# BottomSide.net
KiCad netlist of a schematic drawn in Altium Designer
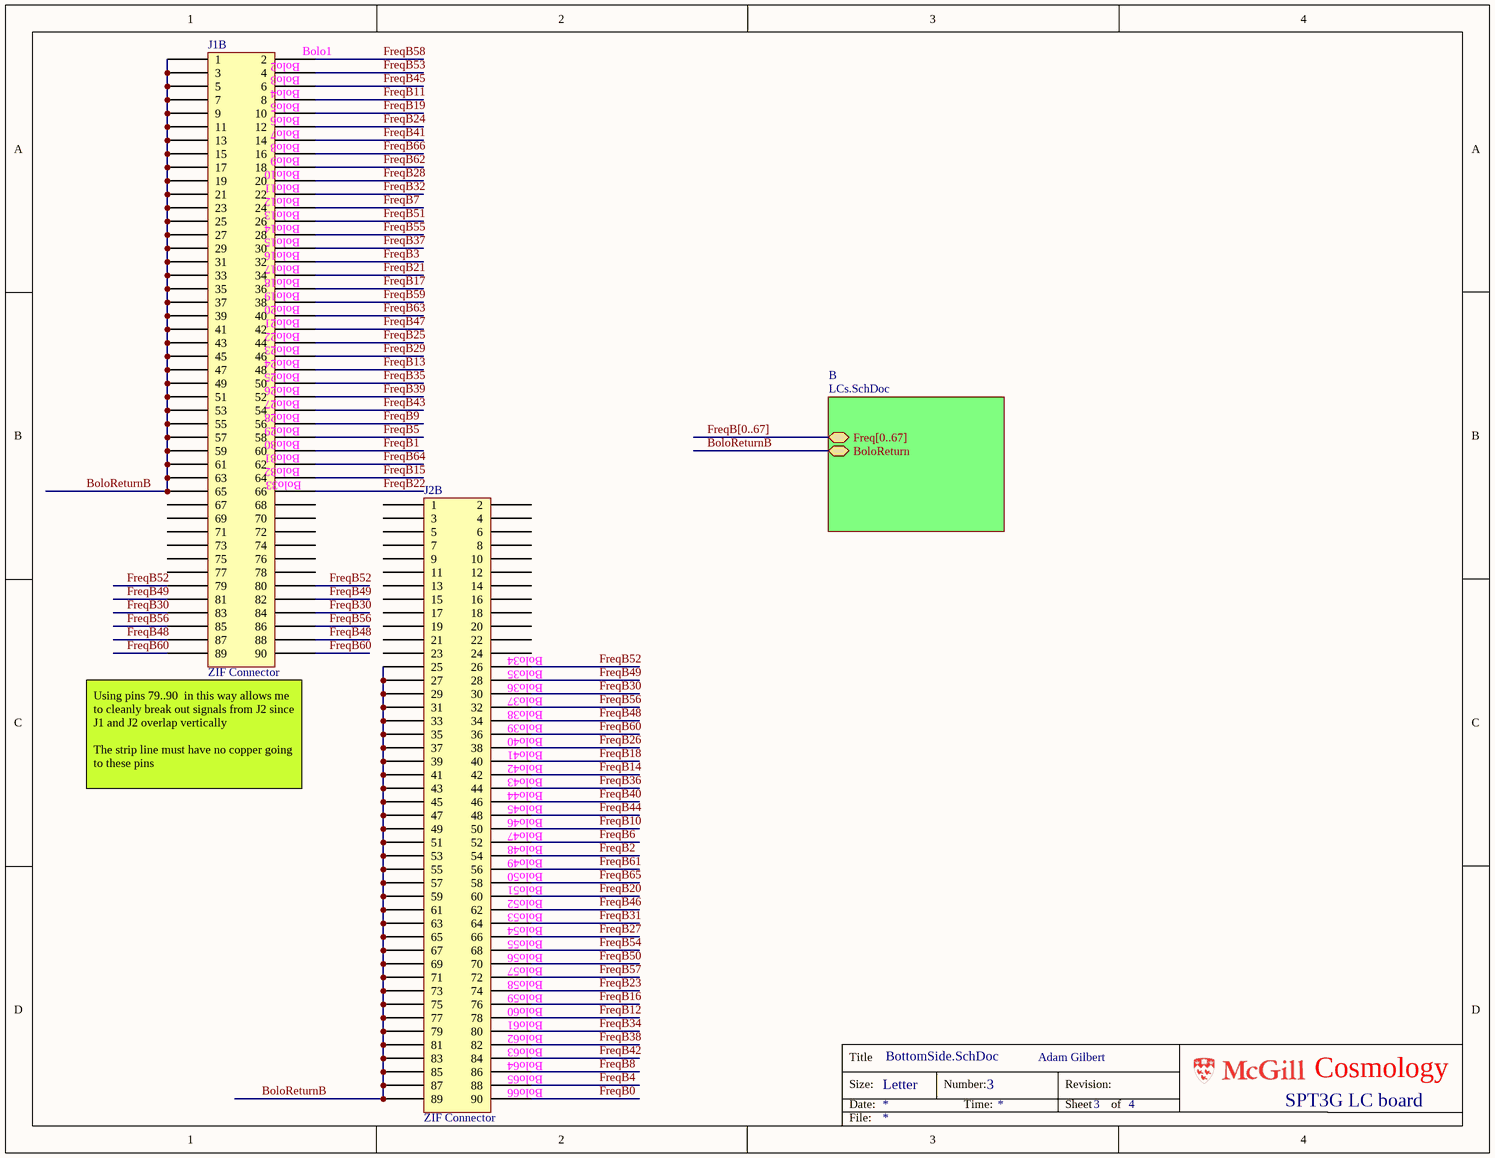
[diagram p0: BottomSide.SchDoc]

(export (version "E")
  (design (tool "Eeschema 10.0.6"))
  (components
    (comp (ref "J1B")
      (value "ZIF Connector")
      (footprint "LCBoard_ZIFCon")
      (libsource (lib "SPT3G_LCBoard") (part "LCboard_FH16-90S-0.3SHW(05)"))
    )
    (comp (ref "J2B")
      (value "ZIF Connector")
      (footprint "LCBoard_ZIFCon")
      (libsource (lib "SPT3G_LCBoard") (part "LCboard_FH16-90S-0.3SHW(05)"))
    )
  )
  (nets
    (net (code "3") (name "/BoloReturnB") (class "Default")
      (node (ref "J1B") (pin "1") (pinfunction "1_1") (pintype "passive"))
      (node (ref "J1B") (pin "11") (pinfunction "11_11") (pintype "passive"))
      (node (ref "J1B") (pin "13") (pinfunction "13_13") (pintype "passive"))
      (node (ref "J1B") (pin "15") (pinfunction "15_15") (pintype "passive"))
      (node (ref "J1B") (pin "17") (pinfunction "17_17") (pintype "passive"))
      (node (ref "J1B") (pin "19") (pinfunction "19_19") (pintype "passive"))
      (node (ref "J1B") (pin "21") (pinfunction "21_21") (pintype "passive"))
      (node (ref "J1B") (pin "23") (pinfunction "23_23") (pintype "passive"))
      (node (ref "J1B") (pin "25") (pinfunction "25_25") (pintype "passive"))
      (node (ref "J1B") (pin "27") (pinfunction "27_27") (pintype "passive"))
      (node (ref "J1B") (pin "29") (pinfunction "29_29") (pintype "passive"))
      (node (ref "J1B") (pin "3") (pinfunction "3_3") (pintype "passive"))
      (node (ref "J1B") (pin "31") (pinfunction "31_31") (pintype "passive"))
      (node (ref "J1B") (pin "33") (pinfunction "33_33") (pintype "passive"))
      (node (ref "J1B") (pin "35") (pinfunction "35_35") (pintype "passive"))
      (node (ref "J1B") (pin "37") (pinfunction "37_37") (pintype "passive"))
      (node (ref "J1B") (pin "39") (pinfunction "39_39") (pintype "passive"))
      (node (ref "J1B") (pin "41") (pinfunction "41_41") (pintype "passive"))
      (node (ref "J1B") (pin "43") (pinfunction "43_43") (pintype "passive"))
      (node (ref "J1B") (pin "45") (pinfunction "45_45") (pintype "passive"))
      (node (ref "J1B") (pin "47") (pinfunction "47_47") (pintype "passive"))
      (node (ref "J1B") (pin "49") (pinfunction "49_49") (pintype "passive"))
      (node (ref "J1B") (pin "5") (pinfunction "5_5") (pintype "passive"))
      (node (ref "J1B") (pin "51") (pinfunction "51_51") (pintype "passive"))
      (node (ref "J1B") (pin "53") (pinfunction "53_53") (pintype "passive"))
      (node (ref "J1B") (pin "55") (pinfunction "55_55") (pintype "passive"))
      (node (ref "J1B") (pin "57") (pinfunction "57_57") (pintype "passive"))
      (node (ref "J1B") (pin "59") (pinfunction "59_59") (pintype "passive"))
      (node (ref "J1B") (pin "61") (pinfunction "61_61") (pintype "passive"))
      (node (ref "J1B") (pin "63") (pinfunction "63_63") (pintype "passive"))
      (node (ref "J1B") (pin "65") (pinfunction "65_65") (pintype "passive"))
      (node (ref "J1B") (pin "7") (pinfunction "7_7") (pintype "passive"))
      (node (ref "J1B") (pin "9") (pinfunction "9_9") (pintype "passive"))
      (node (ref "J2B") (pin "25") (pinfunction "25_25") (pintype "passive"))
      (node (ref "J2B") (pin "27") (pinfunction "27_27") (pintype "passive"))
      (node (ref "J2B") (pin "29") (pinfunction "29_29") (pintype "passive"))
      (node (ref "J2B") (pin "31") (pinfunction "31_31") (pintype "passive"))
      (node (ref "J2B") (pin "33") (pinfunction "33_33") (pintype "passive"))
      (node (ref "J2B") (pin "35") (pinfunction "35_35") (pintype "passive"))
      (node (ref "J2B") (pin "37") (pinfunction "37_37") (pintype "passive"))
      (node (ref "J2B") (pin "39") (pinfunction "39_39") (pintype "passive"))
      (node (ref "J2B") (pin "41") (pinfunction "41_41") (pintype "passive"))
      (node (ref "J2B") (pin "43") (pinfunction "43_43") (pintype "passive"))
      (node (ref "J2B") (pin "45") (pinfunction "45_45") (pintype "passive"))
      (node (ref "J2B") (pin "47") (pinfunction "47_47") (pintype "passive"))
      (node (ref "J2B") (pin "49") (pinfunction "49_49") (pintype "passive"))
      (node (ref "J2B") (pin "51") (pinfunction "51_51") (pintype "passive"))
      (node (ref "J2B") (pin "53") (pinfunction "53_53") (pintype "passive"))
      (node (ref "J2B") (pin "55") (pinfunction "55_55") (pintype "passive"))
      (node (ref "J2B") (pin "57") (pinfunction "57_57") (pintype "passive"))
      (node (ref "J2B") (pin "59") (pinfunction "59_59") (pintype "passive"))
      (node (ref "J2B") (pin "61") (pinfunction "61_61") (pintype "passive"))
      (node (ref "J2B") (pin "63") (pinfunction "63_63") (pintype "passive"))
      (node (ref "J2B") (pin "65") (pinfunction "65_65") (pintype "passive"))
      (node (ref "J2B") (pin "67") (pinfunction "67_67") (pintype "passive"))
      (node (ref "J2B") (pin "69") (pinfunction "69_69") (pintype "passive"))
      (node (ref "J2B") (pin "71") (pinfunction "71_71") (pintype "passive"))
      (node (ref "J2B") (pin "73") (pinfunction "73_73") (pintype "passive"))
      (node (ref "J2B") (pin "75") (pinfunction "75_75") (pintype "passive"))
      (node (ref "J2B") (pin "77") (pinfunction "77_77") (pintype "passive"))
      (node (ref "J2B") (pin "79") (pinfunction "79_79") (pintype "passive"))
      (node (ref "J2B") (pin "81") (pinfunction "81_81") (pintype "passive"))
      (node (ref "J2B") (pin "83") (pinfunction "83_83") (pintype "passive"))
      (node (ref "J2B") (pin "85") (pinfunction "85_85") (pintype "passive"))
      (node (ref "J2B") (pin "87") (pinfunction "87_87") (pintype "passive"))
      (node (ref "J2B") (pin "89") (pinfunction "89_89") (pintype "passive"))
    )
    (net (code "4") (name "/FreqB0") (class "Default")
      (node (ref "J2B") (pin "90") (pinfunction "90_90") (pintype "passive"))
    )
    (net (code "5") (name "/FreqB1") (class "Default")
      (node (ref "J1B") (pin "60") (pinfunction "60_60") (pintype "passive"))
    )
    (net (code "6") (name "/FreqB2") (class "Default")
      (node (ref "J2B") (pin "54") (pinfunction "54_54") (pintype "passive"))
    )
    (net (code "7") (name "/FreqB3") (class "Default")
      (node (ref "J1B") (pin "32") (pinfunction "32_32") (pintype "passive"))
    )
    (net (code "8") (name "/FreqB4") (class "Default")
      (node (ref "J2B") (pin "88") (pinfunction "88_88") (pintype "passive"))
    )
    (net (code "9") (name "/FreqB5") (class "Default")
      (node (ref "J1B") (pin "58") (pinfunction "58_58") (pintype "passive"))
    )
    (net (code "10") (name "/FreqB6") (class "Default")
      (node (ref "J2B") (pin "52") (pinfunction "52_52") (pintype "passive"))
    )
    (net (code "11") (name "/FreqB7") (class "Default")
      (node (ref "J1B") (pin "24") (pinfunction "24_24") (pintype "passive"))
    )
    (net (code "12") (name "/FreqB8") (class "Default")
      (node (ref "J2B") (pin "86") (pinfunction "86_86") (pintype "passive"))
    )
    (net (code "13") (name "/FreqB9") (class "Default")
      (node (ref "J1B") (pin "56") (pinfunction "56_56") (pintype "passive"))
    )
    (net (code "14") (name "/FreqB10") (class "Default")
      (node (ref "J2B") (pin "50") (pinfunction "50_50") (pintype "passive"))
    )
    (net (code "15") (name "/FreqB11") (class "Default")
      (node (ref "J1B") (pin "8") (pinfunction "8_8") (pintype "passive"))
    )
    (net (code "16") (name "/FreqB12") (class "Default")
      (node (ref "J2B") (pin "78") (pinfunction "78_78") (pintype "passive"))
    )
    (net (code "17") (name "/FreqB13") (class "Default")
      (node (ref "J1B") (pin "48") (pinfunction "48_48") (pintype "passive"))
    )
    (net (code "18") (name "/FreqB14") (class "Default")
      (node (ref "J2B") (pin "42") (pinfunction "42_42") (pintype "passive"))
    )
    (net (code "19") (name "/FreqB15") (class "Default")
      (node (ref "J1B") (pin "64") (pinfunction "64_64") (pintype "passive"))
    )
    (net (code "20") (name "/FreqB16") (class "Default")
      (node (ref "J2B") (pin "76") (pinfunction "76_76") (pintype "passive"))
    )
    (net (code "21") (name "/FreqB17") (class "Default")
      (node (ref "J1B") (pin "36") (pinfunction "36_36") (pintype "passive"))
    )
    (net (code "22") (name "/FreqB18") (class "Default")
      (node (ref "J2B") (pin "40") (pinfunction "40_40") (pintype "passive"))
    )
    (net (code "23") (name "/FreqB19") (class "Default")
      (node (ref "J1B") (pin "10") (pinfunction "10_10") (pintype "passive"))
    )
    (net (code "24") (name "/FreqB20") (class "Default")
      (node (ref "J2B") (pin "60") (pinfunction "60_60") (pintype "passive"))
    )
    (net (code "25") (name "/FreqB21") (class "Default")
      (node (ref "J1B") (pin "34") (pinfunction "34_34") (pintype "passive"))
    )
    (net (code "26") (name "/FreqB22") (class "Default")
      (node (ref "J1B") (pin "66") (pinfunction "66_66") (pintype "passive"))
    )
    (net (code "27") (name "/FreqB23") (class "Default")
      (node (ref "J2B") (pin "74") (pinfunction "74_74") (pintype "passive"))
    )
    (net (code "28") (name "/FreqB24") (class "Default")
      (node (ref "J1B") (pin "12") (pinfunction "12_12") (pintype "passive"))
    )
    (net (code "29") (name "/FreqB25") (class "Default")
      (node (ref "J1B") (pin "44") (pinfunction "44_44") (pintype "passive"))
    )
    (net (code "30") (name "/FreqB26") (class "Default")
      (node (ref "J2B") (pin "38") (pinfunction "38_38") (pintype "passive"))
    )
    (net (code "31") (name "/FreqB27") (class "Default")
      (node (ref "J2B") (pin "66") (pinfunction "66_66") (pintype "passive"))
    )
    (net (code "32") (name "/FreqB28") (class "Default")
      (node (ref "J1B") (pin "20") (pinfunction "20_20") (pintype "passive"))
    )
    (net (code "33") (name "/FreqB29") (class "Default")
      (node (ref "J1B") (pin "46") (pinfunction "46_46") (pintype "passive"))
    )
    (net (code "34") (name "/FreqB30") (class "Default")
      (node (ref "J1B") (pin "83") (pinfunction "83_83") (pintype "passive"))
      (node (ref "J1B") (pin "84") (pinfunction "84_84") (pintype "passive"))
      (node (ref "J2B") (pin "30") (pinfunction "30_30") (pintype "passive"))
    )
    (net (code "35") (name "/FreqB31") (class "Default")
      (node (ref "J2B") (pin "64") (pinfunction "64_64") (pintype "passive"))
    )
    (net (code "36") (name "/FreqB32") (class "Default")
      (node (ref "J1B") (pin "22") (pinfunction "22_22") (pintype "passive"))
    )
    (net (code "37") (name "/FreqB34") (class "Default")
      (node (ref "J2B") (pin "80") (pinfunction "80_80") (pintype "passive"))
    )
    (net (code "38") (name "/FreqB35") (class "Default")
      (node (ref "J1B") (pin "50") (pinfunction "50_50") (pintype "passive"))
    )
    (net (code "39") (name "/FreqB36") (class "Default")
      (node (ref "J2B") (pin "44") (pinfunction "44_44") (pintype "passive"))
    )
    (net (code "40") (name "/FreqB37") (class "Default")
      (node (ref "J1B") (pin "30") (pinfunction "30_30") (pintype "passive"))
    )
    (net (code "41") (name "/FreqB38") (class "Default")
      (node (ref "J2B") (pin "82") (pinfunction "82_82") (pintype "passive"))
    )
    (net (code "42") (name "/FreqB39") (class "Default")
      (node (ref "J1B") (pin "52") (pinfunction "52_52") (pintype "passive"))
    )
    (net (code "43") (name "/FreqB40") (class "Default")
      (node (ref "J2B") (pin "46") (pinfunction "46_46") (pintype "passive"))
    )
    (net (code "44") (name "/FreqB41") (class "Default")
      (node (ref "J1B") (pin "14") (pinfunction "14_14") (pintype "passive"))
    )
    (net (code "45") (name "/FreqB42") (class "Default")
      (node (ref "J2B") (pin "84") (pinfunction "84_84") (pintype "passive"))
    )
    (net (code "46") (name "/FreqB43") (class "Default")
      (node (ref "J1B") (pin "54") (pinfunction "54_54") (pintype "passive"))
    )
    (net (code "47") (name "/FreqB44") (class "Default")
      (node (ref "J2B") (pin "48") (pinfunction "48_48") (pintype "passive"))
    )
    (net (code "48") (name "/FreqB45") (class "Default")
      (node (ref "J1B") (pin "6") (pinfunction "6_6") (pintype "passive"))
    )
    (net (code "49") (name "/FreqB46") (class "Default")
      (node (ref "J2B") (pin "62") (pinfunction "62_62") (pintype "passive"))
    )
    (net (code "50") (name "/FreqB47") (class "Default")
      (node (ref "J1B") (pin "42") (pinfunction "42_42") (pintype "passive"))
    )
    (net (code "51") (name "/FreqB48") (class "Default")
      (node (ref "J1B") (pin "87") (pinfunction "87_87") (pintype "passive"))
      (node (ref "J1B") (pin "88") (pinfunction "88_88") (pintype "passive"))
      (node (ref "J2B") (pin "34") (pinfunction "34_34") (pintype "passive"))
    )
    (net (code "52") (name "/FreqB49") (class "Default")
      (node (ref "J1B") (pin "81") (pinfunction "81_81") (pintype "passive"))
      (node (ref "J1B") (pin "82") (pinfunction "82_82") (pintype "passive"))
      (node (ref "J2B") (pin "28") (pinfunction "28_28") (pintype "passive"))
    )
    (net (code "53") (name "/FreqB50") (class "Default")
      (node (ref "J2B") (pin "70") (pinfunction "70_70") (pintype "passive"))
    )
    (net (code "54") (name "/FreqB51") (class "Default")
      (node (ref "J1B") (pin "26") (pinfunction "26_26") (pintype "passive"))
    )
    (net (code "55") (name "/FreqB52") (class "Default")
      (node (ref "J1B") (pin "79") (pinfunction "79_79") (pintype "passive"))
      (node (ref "J1B") (pin "80") (pinfunction "80_80") (pintype "passive"))
      (node (ref "J2B") (pin "26") (pinfunction "26_26") (pintype "passive"))
    )
    (net (code "56") (name "/FreqB53") (class "Default")
      (node (ref "J1B") (pin "4") (pinfunction "4_4") (pintype "passive"))
    )
    (net (code "57") (name "/FreqB54") (class "Default")
      (node (ref "J2B") (pin "68") (pinfunction "68_68") (pintype "passive"))
    )
    (net (code "58") (name "/FreqB55") (class "Default")
      (node (ref "J1B") (pin "28") (pinfunction "28_28") (pintype "passive"))
    )
    (net (code "59") (name "/FreqB56") (class "Default")
      (node (ref "J1B") (pin "85") (pinfunction "85_85") (pintype "passive"))
      (node (ref "J1B") (pin "86") (pinfunction "86_86") (pintype "passive"))
      (node (ref "J2B") (pin "32") (pinfunction "32_32") (pintype "passive"))
    )
    (net (code "60") (name "/FreqB57") (class "Default")
      (node (ref "J2B") (pin "72") (pinfunction "72_72") (pintype "passive"))
    )
    (net (code "61") (name "/FreqB58") (class "Default")
      (node (ref "J1B") (pin "2") (pinfunction "2_2") (pintype "passive"))
    )
    (net (code "62") (name "/FreqB59") (class "Default")
      (node (ref "J1B") (pin "38") (pinfunction "38_38") (pintype "passive"))
    )
    (net (code "63") (name "/FreqB60") (class "Default")
      (node (ref "J1B") (pin "89") (pinfunction "89_89") (pintype "passive"))
      (node (ref "J1B") (pin "90") (pinfunction "90_90") (pintype "passive"))
      (node (ref "J2B") (pin "36") (pinfunction "36_36") (pintype "passive"))
    )
    (net (code "64") (name "/FreqB61") (class "Default")
      (node (ref "J2B") (pin "56") (pinfunction "56_56") (pintype "passive"))
    )
    (net (code "65") (name "/FreqB62") (class "Default")
      (node (ref "J1B") (pin "18") (pinfunction "18_18") (pintype "passive"))
    )
    (net (code "66") (name "/FreqB63") (class "Default")
      (node (ref "J1B") (pin "40") (pinfunction "40_40") (pintype "passive"))
    )
    (net (code "67") (name "/FreqB64") (class "Default")
      (node (ref "J1B") (pin "62") (pinfunction "62_62") (pintype "passive"))
    )
    (net (code "68") (name "/FreqB65") (class "Default")
      (node (ref "J2B") (pin "58") (pinfunction "58_58") (pintype "passive"))
    )
    (net (code "69") (name "/FreqB66") (class "Default")
      (node (ref "J1B") (pin "16") (pinfunction "16_16") (pintype "passive"))
    )
    (net (code "71") (name "unconnected-(J1B-Pad67)") (class "Default")
      (node (ref "J1B") (pin "67") (pinfunction "67_67") (pintype "passive"))
    )
    (net (code "72") (name "unconnected-(J1B-Pad68)") (class "Default")
      (node (ref "J1B") (pin "68") (pinfunction "68_68") (pintype "passive"))
    )
    (net (code "73") (name "unconnected-(J1B-Pad69)") (class "Default")
      (node (ref "J1B") (pin "69") (pinfunction "69_69") (pintype "passive"))
    )
    (net (code "74") (name "unconnected-(J1B-Pad70)") (class "Default")
      (node (ref "J1B") (pin "70") (pinfunction "70_70") (pintype "passive"))
    )
    (net (code "75") (name "unconnected-(J1B-Pad71)") (class "Default")
      (node (ref "J1B") (pin "71") (pinfunction "71_71") (pintype "passive"))
    )
    (net (code "76") (name "unconnected-(J1B-Pad72)") (class "Default")
      (node (ref "J1B") (pin "72") (pinfunction "72_72") (pintype "passive"))
    )
    (net (code "77") (name "unconnected-(J1B-Pad73)") (class "Default")
      (node (ref "J1B") (pin "73") (pinfunction "73_73") (pintype "passive"))
    )
    (net (code "78") (name "unconnected-(J1B-Pad74)") (class "Default")
      (node (ref "J1B") (pin "74") (pinfunction "74_74") (pintype "passive"))
    )
    (net (code "79") (name "unconnected-(J1B-Pad75)") (class "Default")
      (node (ref "J1B") (pin "75") (pinfunction "75_75") (pintype "passive"))
    )
    (net (code "80") (name "unconnected-(J1B-Pad76)") (class "Default")
      (node (ref "J1B") (pin "76") (pinfunction "76_76") (pintype "passive"))
    )
    (net (code "81") (name "unconnected-(J1B-Pad77)") (class "Default")
      (node (ref "J1B") (pin "77") (pinfunction "77_77") (pintype "passive"))
    )
    (net (code "82") (name "unconnected-(J1B-Pad78)") (class "Default")
      (node (ref "J1B") (pin "78") (pinfunction "78_78") (pintype "passive"))
    )
    (net (code "83") (name "unconnected-(J2B-Pad1)") (class "Default")
      (node (ref "J2B") (pin "1") (pinfunction "1_1") (pintype "passive"))
    )
    (net (code "84") (name "unconnected-(J2B-Pad2)") (class "Default")
      (node (ref "J2B") (pin "2") (pinfunction "2_2") (pintype "passive"))
    )
    (net (code "85") (name "unconnected-(J2B-Pad3)") (class "Default")
      (node (ref "J2B") (pin "3") (pinfunction "3_3") (pintype "passive"))
    )
    (net (code "86") (name "unconnected-(J2B-Pad4)") (class "Default")
      (node (ref "J2B") (pin "4") (pinfunction "4_4") (pintype "passive"))
    )
    (net (code "87") (name "unconnected-(J2B-Pad5)") (class "Default")
      (node (ref "J2B") (pin "5") (pinfunction "5_5") (pintype "passive"))
    )
    (net (code "88") (name "unconnected-(J2B-Pad6)") (class "Default")
      (node (ref "J2B") (pin "6") (pinfunction "6_6") (pintype "passive"))
    )
    (net (code "89") (name "unconnected-(J2B-Pad7)") (class "Default")
      (node (ref "J2B") (pin "7") (pinfunction "7_7") (pintype "passive"))
    )
    (net (code "90") (name "unconnected-(J2B-Pad8)") (class "Default")
      (node (ref "J2B") (pin "8") (pinfunction "8_8") (pintype "passive"))
    )
    (net (code "91") (name "unconnected-(J2B-Pad9)") (class "Default")
      (node (ref "J2B") (pin "9") (pinfunction "9_9") (pintype "passive"))
    )
    (net (code "92") (name "unconnected-(J2B-Pad10)") (class "Default")
      (node (ref "J2B") (pin "10") (pinfunction "10_10") (pintype "passive"))
    )
    (net (code "93") (name "unconnected-(J2B-Pad11)") (class "Default")
      (node (ref "J2B") (pin "11") (pinfunction "11_11") (pintype "passive"))
    )
    (net (code "94") (name "unconnected-(J2B-Pad12)") (class "Default")
      (node (ref "J2B") (pin "12") (pinfunction "12_12") (pintype "passive"))
    )
    (net (code "95") (name "unconnected-(J2B-Pad13)") (class "Default")
      (node (ref "J2B") (pin "13") (pinfunction "13_13") (pintype "passive"))
    )
    (net (code "96") (name "unconnected-(J2B-Pad14)") (class "Default")
      (node (ref "J2B") (pin "14") (pinfunction "14_14") (pintype "passive"))
    )
    (net (code "97") (name "unconnected-(J2B-Pad15)") (class "Default")
      (node (ref "J2B") (pin "15") (pinfunction "15_15") (pintype "passive"))
    )
    (net (code "98") (name "unconnected-(J2B-Pad16)") (class "Default")
      (node (ref "J2B") (pin "16") (pinfunction "16_16") (pintype "passive"))
    )
    (net (code "99") (name "unconnected-(J2B-Pad17)") (class "Default")
      (node (ref "J2B") (pin "17") (pinfunction "17_17") (pintype "passive"))
    )
    (net (code "100") (name "unconnected-(J2B-Pad18)") (class "Default")
      (node (ref "J2B") (pin "18") (pinfunction "18_18") (pintype "passive"))
    )
    (net (code "101") (name "unconnected-(J2B-Pad19)") (class "Default")
      (node (ref "J2B") (pin "19") (pinfunction "19_19") (pintype "passive"))
    )
    (net (code "102") (name "unconnected-(J2B-Pad20)") (class "Default")
      (node (ref "J2B") (pin "20") (pinfunction "20_20") (pintype "passive"))
    )
    (net (code "103") (name "unconnected-(J2B-Pad21)") (class "Default")
      (node (ref "J2B") (pin "21") (pinfunction "21_21") (pintype "passive"))
    )
    (net (code "104") (name "unconnected-(J2B-Pad22)") (class "Default")
      (node (ref "J2B") (pin "22") (pinfunction "22_22") (pintype "passive"))
    )
    (net (code "105") (name "unconnected-(J2B-Pad23)") (class "Default")
      (node (ref "J2B") (pin "23") (pinfunction "23_23") (pintype "passive"))
    )
    (net (code "106") (name "unconnected-(J2B-Pad24)") (class "Default")
      (node (ref "J2B") (pin "24") (pinfunction "24_24") (pintype "passive"))
    )
  )
)
